# WiringDiagram.net
KiCad netlist of a schematic drawn in EAGLE
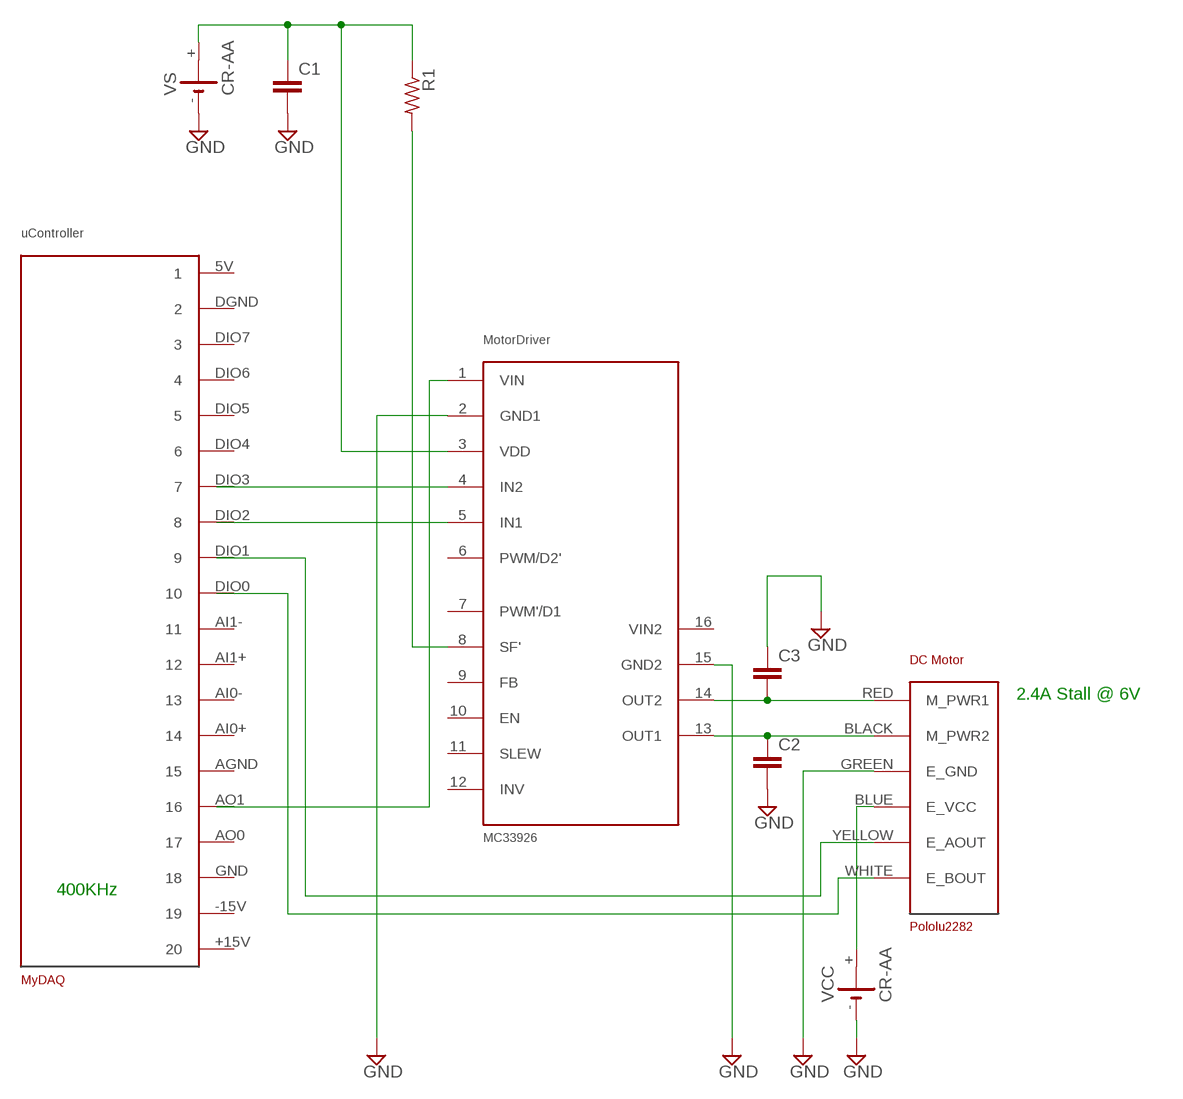
[diagram p0: schematic, sheet 1]

(export (version "E")
  (design (tool "Eeschema 10.0.6"))
  (components
    (comp (ref "C1")
      (value "C2,5-3")
      (footprint "eagle-import:C2.5-3")
      (libsource (lib "eagle-import") (part "C2,5-3"))
    )
    (comp (ref "C2")
      (value "C2,5-3")
      (footprint "eagle-import:C2.5-3")
      (libsource (lib "eagle-import") (part "C2,5-3"))
    )
    (comp (ref "C3")
      (value "C2,5-3")
      (footprint "eagle-import:C2.5-3")
      (libsource (lib "eagle-import") (part "C2,5-3"))
    )
    (comp (ref "R1")
      (value "R-US_0204/2V")
      (footprint "eagle-import:0204V")
      (libsource (lib "eagle-import") (part "R-US_0204/2V"))
    )
    (comp (ref "U$1")
      (value "MC33926")
      (footprint "eagle-import:MC33926")
      (libsource (lib "eagle-import") (part "MC33926"))
    )
    (comp (ref "U$2")
      (value "DCMOTOR")
      (footprint "eagle-import:DCMOTOR")
      (libsource (lib "eagle-import") (part "DCMOTOR"))
    )
    (comp (ref "U$3")
      (value "MYDAQ")
      (footprint "eagle-import:MYDAQ")
      (libsource (lib "eagle-import") (part "MYDAQ"))
    )
    (comp (ref "VCC")
      (value "CR-AA")
      (footprint "eagle-import:CRAA")
      (libsource (lib "eagle-import") (part "CR-AA"))
    )
    (comp (ref "VS")
      (value "CR-AA")
      (footprint "eagle-import:CRAA")
      (libsource (lib "eagle-import") (part "CR-AA"))
    )
  )
  (nets
    (net (code "1") (name "GND") (class "Default")
      (node (ref "C1") (pin "2") (pinfunction "2_2") (pintype "passive"))
      (node (ref "C2") (pin "2") (pinfunction "2_2") (pintype "passive"))
      (node (ref "C3") (pin "1") (pinfunction "1_1") (pintype "passive"))
      (node (ref "U$1") (pin "15") (pinfunction "GND2_15") (pintype "bidirectional"))
      (node (ref "U$1") (pin "2") (pinfunction "GND1_2") (pintype "bidirectional"))
      (node (ref "U$2") (pin "GREEN") (pinfunction "E_GND_GREEN") (pintype "bidirectional"))
      (node (ref "VCC") (pin "-") (pinfunction "-_-") (pintype "passive"))
      (node (ref "VS") (pin "-") (pinfunction "-_-") (pintype "passive"))
    )
    (net (code "2") (name "Net-(U$1-OUT1)") (class "Default")
      (node (ref "C2") (pin "1") (pinfunction "1_1") (pintype "passive"))
      (node (ref "U$1") (pin "13") (pinfunction "OUT1_13") (pintype "bidirectional"))
      (node (ref "U$2") (pin "BLACK") (pinfunction "M_PWR2_BLACK") (pintype "bidirectional"))
    )
    (net (code "3") (name "Net-(U$1-OUT2)") (class "Default")
      (node (ref "C3") (pin "2") (pinfunction "2_2") (pintype "passive"))
      (node (ref "U$1") (pin "14") (pinfunction "OUT2_14") (pintype "bidirectional"))
      (node (ref "U$2") (pin "RED") (pinfunction "M_PWR1_RED") (pintype "bidirectional"))
    )
    (net (code "4") (name "Net-(U$1-SF')") (class "Default")
      (node (ref "R1") (pin "2") (pinfunction "2_2") (pintype "passive"))
      (node (ref "U$1") (pin "8") (pinfunction "SF'_8") (pintype "bidirectional"))
    )
    (net (code "5") (name "Net-(U$1-VDD)") (class "Default")
      (node (ref "C1") (pin "1") (pinfunction "1_1") (pintype "passive"))
      (node (ref "R1") (pin "1") (pinfunction "1_1") (pintype "passive"))
      (node (ref "U$1") (pin "3") (pinfunction "VDD_3") (pintype "bidirectional"))
      (node (ref "VS") (pin "+") (pinfunction "+_+") (pintype "passive"))
    )
    (net (code "6") (name "Net-(U$2-E_VCC)") (class "Default")
      (node (ref "U$2") (pin "BLUE") (pinfunction "E_VCC_BLUE") (pintype "bidirectional"))
      (node (ref "VCC") (pin "+") (pinfunction "+_+") (pintype "passive"))
    )
    (net (code "7") (name "unconnected-(U$1-EN-Pad10)") (class "Default")
      (node (ref "U$1") (pin "10") (pinfunction "EN_10") (pintype "bidirectional"))
    )
    (net (code "8") (name "unconnected-(U$1-FB-Pad9)") (class "Default")
      (node (ref "U$1") (pin "9") (pinfunction "FB_9") (pintype "bidirectional"))
    )
    (net (code "9") (name "unconnected-(U$1-IN1-Pad5)") (class "Default")
      (node (ref "U$1") (pin "5") (pinfunction "IN1_5") (pintype "bidirectional"))
    )
    (net (code "10") (name "unconnected-(U$1-IN2-Pad4)") (class "Default")
      (node (ref "U$1") (pin "4") (pinfunction "IN2_4") (pintype "bidirectional"))
    )
    (net (code "11") (name "unconnected-(U$1-INV-Pad12)") (class "Default")
      (node (ref "U$1") (pin "12") (pinfunction "INV_12") (pintype "bidirectional"))
    )
    (net (code "12") (name "unconnected-(U$1-PWM'{slash}D1-Pad7)") (class "Default")
      (node (ref "U$1") (pin "7") (pinfunction "PWM'/D1_7") (pintype "bidirectional"))
    )
    (net (code "13") (name "unconnected-(U$1-PWM{slash}D2'-Pad6)") (class "Default")
      (node (ref "U$1") (pin "6") (pinfunction "PWM/D2'_6") (pintype "bidirectional"))
    )
    (net (code "14") (name "unconnected-(U$1-SLEW-Pad11)") (class "Default")
      (node (ref "U$1") (pin "11") (pinfunction "SLEW_11") (pintype "bidirectional"))
    )
    (net (code "15") (name "unconnected-(U$1-VIN-Pad1)") (class "Default")
      (node (ref "U$1") (pin "1") (pinfunction "VIN_1") (pintype "bidirectional"))
    )
    (net (code "16") (name "unconnected-(U$1-VIN2-Pad16)") (class "Default")
      (node (ref "U$1") (pin "16") (pinfunction "VIN2_16") (pintype "bidirectional"))
    )
    (net (code "17") (name "unconnected-(U$2-E_AOUT-PadYELLOW)") (class "Default")
      (node (ref "U$2") (pin "YELLOW") (pinfunction "E_AOUT_YELLOW") (pintype "bidirectional"))
    )
    (net (code "18") (name "unconnected-(U$2-E_BOUT-PadWHITE)") (class "Default")
      (node (ref "U$2") (pin "WHITE") (pinfunction "E_BOUT_WHITE") (pintype "bidirectional"))
    )
    (net (code "19") (name "unconnected-(U$3-1-Pad5V)") (class "Default")
      (node (ref "U$3") (pin "5V") (pinfunction "1_5V") (pintype "bidirectional"))
    )
    (net (code "20") (name "unconnected-(U$3-2-PadDGND)") (class "Default")
      (node (ref "U$3") (pin "DGND") (pinfunction "2_DGND") (pintype "bidirectional"))
    )
    (net (code "21") (name "unconnected-(U$3-3-PadDIO7)") (class "Default")
      (node (ref "U$3") (pin "DIO7") (pinfunction "3_DIO7") (pintype "bidirectional"))
    )
    (net (code "22") (name "unconnected-(U$3-4-PadDIO6)") (class "Default")
      (node (ref "U$3") (pin "DIO6") (pinfunction "4_DIO6") (pintype "bidirectional"))
    )
    (net (code "23") (name "unconnected-(U$3-5-PadDIO5)") (class "Default")
      (node (ref "U$3") (pin "DIO5") (pinfunction "5_DIO5") (pintype "bidirectional"))
    )
    (net (code "24") (name "unconnected-(U$3-6-PadDIO4)") (class "Default")
      (node (ref "U$3") (pin "DIO4") (pinfunction "6_DIO4") (pintype "bidirectional"))
    )
    (net (code "25") (name "unconnected-(U$3-7-PadDIO3)") (class "Default")
      (node (ref "U$3") (pin "DIO3") (pinfunction "7_DIO3") (pintype "bidirectional"))
    )
    (net (code "26") (name "unconnected-(U$3-8-PadDIO2)") (class "Default")
      (node (ref "U$3") (pin "DIO2") (pinfunction "8_DIO2") (pintype "bidirectional"))
    )
    (net (code "27") (name "unconnected-(U$3-9-PadDIO1)") (class "Default")
      (node (ref "U$3") (pin "DIO1") (pinfunction "9_DIO1") (pintype "bidirectional"))
    )
    (net (code "28") (name "unconnected-(U$3-10-PadDIO0)") (class "Default")
      (node (ref "U$3") (pin "DIO0") (pinfunction "10_DIO0") (pintype "bidirectional"))
    )
    (net (code "29") (name "unconnected-(U$3-11-PadAI1-)") (class "Default")
      (node (ref "U$3") (pin "AI1-") (pinfunction "11_AI1-") (pintype "bidirectional"))
    )
    (net (code "30") (name "unconnected-(U$3-12-PadAI1+)") (class "Default")
      (node (ref "U$3") (pin "AI1+") (pinfunction "12_AI1+") (pintype "bidirectional"))
    )
    (net (code "31") (name "unconnected-(U$3-13-PadAI0-)") (class "Default")
      (node (ref "U$3") (pin "AI0-") (pinfunction "13_AI0-") (pintype "bidirectional"))
    )
    (net (code "32") (name "unconnected-(U$3-14-PadAI0+)") (class "Default")
      (node (ref "U$3") (pin "AI0+") (pinfunction "14_AI0+") (pintype "bidirectional"))
    )
    (net (code "33") (name "unconnected-(U$3-15-PadAGND)") (class "Default")
      (node (ref "U$3") (pin "AGND") (pinfunction "15_AGND") (pintype "bidirectional"))
    )
    (net (code "34") (name "unconnected-(U$3-16-PadAO1)") (class "Default")
      (node (ref "U$3") (pin "AO1") (pinfunction "16_AO1") (pintype "bidirectional"))
    )
    (net (code "35") (name "unconnected-(U$3-17-PadAO0)") (class "Default")
      (node (ref "U$3") (pin "AO0") (pinfunction "17_AO0") (pintype "bidirectional"))
    )
    (net (code "36") (name "unconnected-(U$3-18-PadGND)") (class "Default")
      (node (ref "U$3") (pin "GND") (pinfunction "18_GND") (pintype "bidirectional"))
    )
    (net (code "37") (name "unconnected-(U$3-19-Pad-15V)") (class "Default")
      (node (ref "U$3") (pin "-15V") (pinfunction "19_-15V") (pintype "bidirectional"))
    )
    (net (code "38") (name "unconnected-(U$3-20-Pad+15V)") (class "Default")
      (node (ref "U$3") (pin "+15V") (pinfunction "20_+15V") (pintype "bidirectional"))
    )
    (net (code "39") (name "unconnected-(VCC-+-Pad+@1)") (class "Default")
      (node (ref "VCC") (pin "+@1") (pinfunction "+_+@1") (pintype "passive"))
    )
    (net (code "40") (name "unconnected-(VS-+-Pad+@1)") (class "Default")
      (node (ref "VS") (pin "+@1") (pinfunction "+_+@1") (pintype "passive"))
    )
  )
)
